# hv_can.net
KiCad netlist of a schematic drawn in Altium Designer
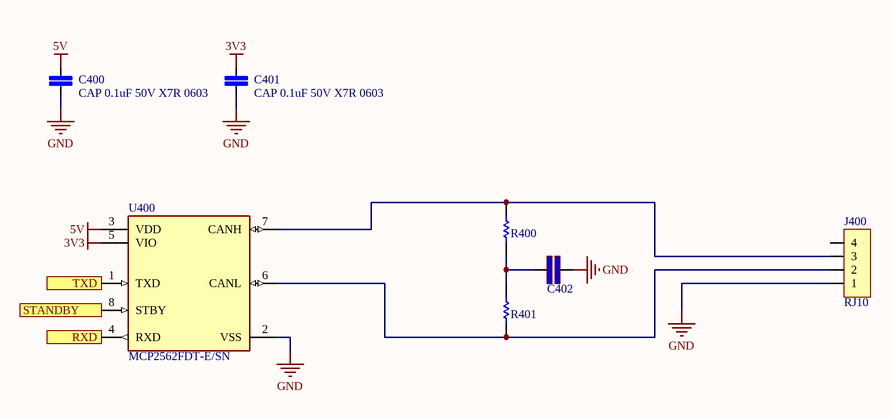
[diagram p0: hv_can.SchDoc]

(export (version "E")
  (design (tool "Eeschema 10.0.6"))
  (components
    (comp (ref "C400")
      (value "CAP 0.1uF 50V X7R 0603")
      (footprint "FP-CL10-IPC_B")
      (description "Cap Ceramic 0.1uF 50V X7R 20% SMD 0603 125C Paper T/R")
      (libsource (lib "StackFoundry LLC") (part "C-EU"))
    )
    (comp (ref "C401")
      (value "CAP 0.1uF 50V X7R 0603")
      (footprint "FP-CL10-IPC_B")
      (description "Cap Ceramic 0.1uF 50V X7R 20% SMD 0603 125C Paper T/R")
      (libsource (lib "StackFoundry LLC") (part "C-EU"))
    )
    (comp (ref "C402")
      (value "CAP 4.7uF 50V X7R 1210")
      (footprint "CAPC3225X20N")
      (description "CAP CER 4.7UF 50V X7R 1210")
      (fields (field (name "TOLERANCE") "10%") (field (name "VOLTAGE") "50V"))
      (libsource (lib "StackFoundry LLC") (part "4.7uF"))
    )
    (comp (ref "J400")
      (value "RJ10")
      (footprint "0432024101")
      (description "Modular Connectors / Ethernet Connectors RA 4/4 PORT 1 low profile")
      (libsource (lib "StackFoundry LLC") (part "RJ10"))
    )
    (comp (ref "R400")
      (value "62R 1206 5%")
      (footprint "RESC3116X65X40ML10T20")
      (description "RES SMD 62 OHM 5% 1/4W 1206")
      (fields (field (name "TOLERANCE") "5%"))
      (libsource (lib "StackFoundry LLC") (part "RES"))
    )
    (comp (ref "R401")
      (value "62R 1206 5%")
      (footprint "RESC3116X65X40ML10T20")
      (description "RES SMD 62 OHM 5% 1/4W 1206")
      (fields (field (name "TOLERANCE") "5%"))
      (libsource (lib "StackFoundry LLC") (part "RES"))
    )
    (comp (ref "U400")
      (value "MCP2562FDT-E/SN")
      (footprint "FP-C04-057-SN-MFG")
      (description "IC TRANSCEIVER CAN FLEX 8SOIC")
      (libsource (lib "StackFoundry LLC") (part "fcb6c66e4429206983adab9201371df"))
    )
  )
  (nets
    (net (code "1") (name "/RXD") (class "Default")
      (node (ref "U400") (pin "4") (pinfunction "RXD_4") (pintype "output"))
    )
    (net (code "2") (name "/STANDBY") (class "Default")
      (node (ref "U400") (pin "8") (pinfunction "STBY_8") (pintype "input"))
    )
    (net (code "3") (name "/TXD") (class "Default")
      (node (ref "U400") (pin "1") (pinfunction "TXD_1") (pintype "input"))
    )
    (net (code "4") (name "3V3") (class "Default")
      (node (ref "C401") (pin "1") (pinfunction "1_1") (pintype "passive"))
      (node (ref "U400") (pin "5") (pinfunction "VIO_5") (pintype "power_in"))
    )
    (net (code "5") (name "5V") (class "Default")
      (node (ref "C400") (pin "1") (pinfunction "1_1") (pintype "passive"))
      (node (ref "U400") (pin "3") (pinfunction "VDD_3") (pintype "power_in"))
    )
    (net (code "6") (name "GND") (class "Default")
      (node (ref "C400") (pin "2") (pinfunction "2_2") (pintype "passive"))
      (node (ref "C401") (pin "2") (pinfunction "2_2") (pintype "passive"))
      (node (ref "C402") (pin "1") (pintype "passive"))
      (node (ref "J400") (pin "1") (pinfunction "1_1") (pintype "passive"))
      (node (ref "U400") (pin "2") (pinfunction "VSS_2") (pintype "power_in"))
    )
    (net (code "7") (name "Net-(C402-Pad2)") (class "Default")
      (node (ref "C402") (pin "2") (pintype "passive"))
      (node (ref "R400") (pin "1") (pinfunction "1_1") (pintype "passive"))
      (node (ref "R401") (pin "2") (pinfunction "2_2") (pintype "passive"))
    )
    (net (code "8") (name "Net-(U400-CANH)") (class "Default")
      (node (ref "J400") (pin "3") (pinfunction "3_3") (pintype "passive"))
      (node (ref "R400") (pin "2") (pinfunction "2_2") (pintype "passive"))
      (node (ref "U400") (pin "7") (pinfunction "CANH_7") (pintype "bidirectional"))
    )
    (net (code "9") (name "Net-(U400-CANL)") (class "Default")
      (node (ref "J400") (pin "2") (pinfunction "2_2") (pintype "passive"))
      (node (ref "R401") (pin "1") (pinfunction "1_1") (pintype "passive"))
      (node (ref "U400") (pin "6") (pinfunction "CANL_6") (pintype "bidirectional"))
    )
    (net (code "10") (name "unconnected-(J400-Pad4)") (class "Default")
      (node (ref "J400") (pin "4") (pinfunction "4_4") (pintype "passive"))
    )
  )
)
